# ACMotor_Control.net
KiCad netlist of a schematic drawn in Altium Designer
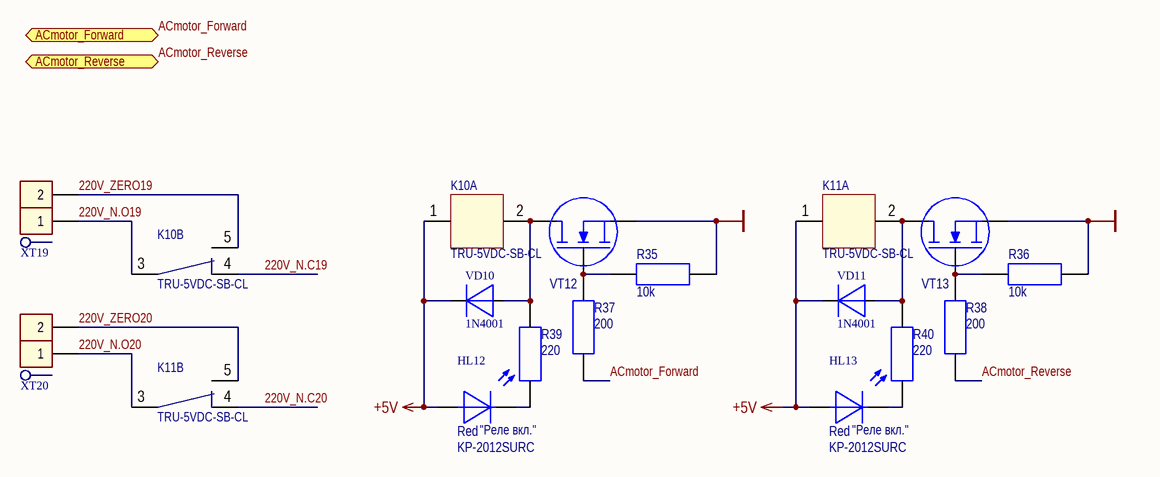
[diagram p0: ACMotor_Control.SchDoc]

(export (version "E")
  (design (tool "Eeschema 10.0.6"))
  (components
    (comp (ref "HL12")
      (value "Red")
      (footprint "Indicator:DIOMELF2012M")
      (description "Diod LED SMD Red")
      (fields (field (name "MANUFACTURERPARTNUMBER") "KP-2012SURC"))
      (libsource (lib "Indicator") (part "LED1_R"))
    )
    (comp (ref "HL13")
      (value "Red")
      (footprint "Indicator:DIOMELF2012M")
      (description "Diod LED SMD Red")
      (fields (field (name "MANUFACTURERPARTNUMBER") "KP-2012SURC"))
      (libsource (lib "Indicator") (part "LED1_R"))
    )
    (comp (ref "K10")
      (value "TRU-5VDC-SB-CL")
      (footprint "Switch:TRU-5VDC-SB-CL")
      (libsource (lib "Switch") (part "TRU-5VDC-SB-CL"))
    )
    (comp (ref "K11")
      (value "TRU-5VDC-SB-CL")
      (footprint "Switch:TRU-5VDC-SB-CL")
      (libsource (lib "Switch") (part "TRU-5VDC-SB-CL"))
    )
    (comp (ref "R35")
      (value "10k")
      (footprint "SMDRC0805")
      (description "Generic resistor")
      (fields (field (name "PARTNUMBER") "Resistor 0805 10k"))
      (libsource (lib "") (part "Resistor_1"))
    )
    (comp (ref "R36")
      (value "10k")
      (footprint "SMDRC0805")
      (description "Generic resistor")
      (fields (field (name "PARTNUMBER") "Resistor 0805 10k"))
      (libsource (lib "") (part "Resistor_1"))
    )
    (comp (ref "R37")
      (value "200")
      (footprint "SMDRC0805")
      (description "Generic resistor")
      (fields (field (name "PARTNUMBER") "Resistor 0805 200"))
      (libsource (lib "") (part "Resistor_2"))
    )
    (comp (ref "R38")
      (value "200")
      (footprint "SMDRC0805")
      (description "Generic resistor")
      (fields (field (name "PARTNUMBER") "Resistor 0805 200"))
      (libsource (lib "") (part "Resistor_2"))
    )
    (comp (ref "R39")
      (value "220")
      (footprint "SMDRC0805")
      (description "Generic resistor")
      (fields (field (name "PARTNUMBER") "Resistor 0805 220"))
      (libsource (lib "library") (part "Resistor"))
    )
    (comp (ref "R40")
      (value "220")
      (footprint "SMDRC0805")
      (description "Generic resistor")
      (fields (field (name "PARTNUMBER") "Resistor 0805 220"))
      (libsource (lib "library") (part "Resistor"))
    )
    (comp (ref "VD10")
      (value "1N4001")
      (footprint "DIod:PinDiode")
      (description "Rectifying diode")
      (fields (field (name "MANUFACTURERPARTNUMBER") "1N4001"))
      (libsource (lib "Diod") (part "1N4001"))
    )
    (comp (ref "VD11")
      (value "1N4001")
      (footprint "DIod:PinDiode")
      (description "Rectifying diode")
      (fields (field (name "MANUFACTURERPARTNUMBER") "1N4001"))
      (libsource (lib "Diod") (part "1N4001"))
    )
    (comp (ref "VT12")
      (value "2N7002")
      (footprint "Standard:SOT23 (TO-236AB)")
      (description "60V, 300mA N-channel Trench MOSFET")
      (libsource (lib "Transistor") (part "2N7002 n-MOSFET"))
    )
    (comp (ref "VT13")
      (value "2N7002")
      (footprint "Standard:SOT23 (TO-236AB)")
      (description "60V, 300mA N-channel Trench MOSFET")
      (libsource (lib "Transistor") (part "2N7002 n-MOSFET"))
    )
    (comp (ref "XT19")
      (value "305-021-12")
      (footprint "330-021-12")
      (description "Demountable connection  2-pin")
      (fields (field (name "MANUFACTURER") "Degson Electronics Co., Ltd"))
      (libsource (lib "Connector") (part "Con2_D 330-021-12"))
    )
    (comp (ref "XT20")
      (value "305-021-12")
      (footprint "330-021-12")
      (description "Demountable connection  2-pin")
      (fields (field (name "MANUFACTURER") "Degson Electronics Co., Ltd"))
      (libsource (lib "Connector") (part "Con2_D 330-021-12"))
    )
  )
  (nets
    (net (code "1") (name "+5V") (class "Default")
      (node (ref "HL12") (pin "1") (pinfunction "1_1") (pintype "passive"))
      (node (ref "HL13") (pin "1") (pinfunction "1_1") (pintype "passive"))
      (node (ref "K10") (pin "1") (pinfunction "1_1") (pintype "passive"))
      (node (ref "K11") (pin "1") (pinfunction "1_1") (pintype "passive"))
      (node (ref "VD10") (pin "K") (pinfunction "K_K") (pintype "passive"))
      (node (ref "VD11") (pin "K") (pinfunction "K_K") (pintype "passive"))
    )
    (net (code "2") (name "/220V_N.C19") (class "Default")
      (node (ref "K10") (pin "4") (pinfunction "4_4") (pintype "passive"))
    )
    (net (code "3") (name "/220V_N.C20") (class "Default")
      (node (ref "K11") (pin "4") (pinfunction "4_4") (pintype "passive"))
    )
    (net (code "4") (name "/220V_N.O19") (class "Default")
      (node (ref "K10") (pin "3") (pinfunction "3_3") (pintype "passive"))
      (node (ref "XT19") (pin "1") (pinfunction "1_1") (pintype "passive"))
    )
    (net (code "5") (name "/220V_N.O20") (class "Default")
      (node (ref "K11") (pin "3") (pinfunction "3_3") (pintype "passive"))
      (node (ref "XT20") (pin "1") (pinfunction "1_1") (pintype "passive"))
    )
    (net (code "6") (name "/220V_ZERO19") (class "Default")
      (node (ref "K10") (pin "5") (pinfunction "5_5") (pintype "passive"))
      (node (ref "XT19") (pin "2") (pinfunction "2_2") (pintype "passive"))
    )
    (net (code "7") (name "/220V_ZERO20") (class "Default")
      (node (ref "K11") (pin "5") (pinfunction "5_5") (pintype "passive"))
      (node (ref "XT20") (pin "2") (pinfunction "2_2") (pintype "passive"))
    )
    (net (code "8") (name "/ACmotor_Forward") (class "Default")
      (node (ref "R37") (pin "1") (pinfunction "1_1") (pintype "passive"))
    )
    (net (code "9") (name "/ACmotor_Reverse") (class "Default")
      (node (ref "R38") (pin "1") (pinfunction "1_1") (pintype "passive"))
    )
    (net (code "10") (name "GND") (class "Default")
      (node (ref "R35") (pin "2") (pinfunction "2_2") (pintype "passive"))
      (node (ref "R36") (pin "2") (pinfunction "2_2") (pintype "passive"))
      (node (ref "VT12") (pin "2") (pinfunction "S_2") (pintype "passive"))
      (node (ref "VT13") (pin "2") (pinfunction "S_2") (pintype "passive"))
    )
    (net (code "11") (name "Net-(HL12-Pad2)") (class "Default")
      (node (ref "HL12") (pin "2") (pinfunction "2_2") (pintype "passive"))
      (node (ref "R39") (pin "2") (pinfunction "2_2") (pintype "passive"))
    )
    (net (code "12") (name "Net-(HL13-Pad2)") (class "Default")
      (node (ref "HL13") (pin "2") (pinfunction "2_2") (pintype "passive"))
      (node (ref "R40") (pin "2") (pinfunction "2_2") (pintype "passive"))
    )
    (net (code "13") (name "Net-(VT12-D)") (class "Default")
      (node (ref "K10") (pin "2") (pinfunction "2_2") (pintype "passive"))
      (node (ref "R39") (pin "1") (pinfunction "1_1") (pintype "passive"))
      (node (ref "VD10") (pin "A") (pinfunction "A_A") (pintype "passive"))
      (node (ref "VT12") (pin "3") (pinfunction "D_3") (pintype "passive"))
    )
    (net (code "14") (name "Net-(VT12-G)") (class "Default")
      (node (ref "R35") (pin "1") (pinfunction "1_1") (pintype "passive"))
      (node (ref "R37") (pin "2") (pinfunction "2_2") (pintype "passive"))
      (node (ref "VT12") (pin "1") (pinfunction "G_1") (pintype "passive"))
    )
    (net (code "15") (name "Net-(VT13-D)") (class "Default")
      (node (ref "K11") (pin "2") (pinfunction "2_2") (pintype "passive"))
      (node (ref "R40") (pin "1") (pinfunction "1_1") (pintype "passive"))
      (node (ref "VD11") (pin "A") (pinfunction "A_A") (pintype "passive"))
      (node (ref "VT13") (pin "3") (pinfunction "D_3") (pintype "passive"))
    )
    (net (code "16") (name "Net-(VT13-G)") (class "Default")
      (node (ref "R36") (pin "1") (pinfunction "1_1") (pintype "passive"))
      (node (ref "R38") (pin "2") (pinfunction "2_2") (pintype "passive"))
      (node (ref "VT13") (pin "1") (pinfunction "G_1") (pintype "passive"))
    )
  )
)
